# 04_CONNECTOR_OUT.net
KiCad netlist of a schematic drawn in Altium Designer
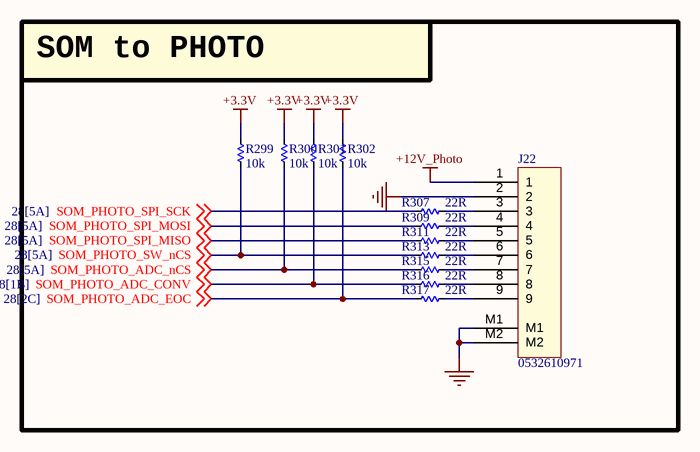
[diagram p0: 04_CONNECTOR_OUT.SchDoc]

(export (version "E")
  (design (tool "Eeschema 10.0.6"))
  (components
    (comp (ref "J22")
      (value "0532610971")
      (footprint "MOLEX_0532610971")
      (libsource (lib "LABLIB") (part "Header 9x1_2M"))
    )
    (comp (ref "R299")
      (value "10k")
      (footprint "RES_C_1005X40")
      (description "RES")
      (libsource (lib "LABLIB") (part "_RES_B_2"))
    )
    (comp (ref "R300")
      (value "10k")
      (footprint "RES_C_1005X40")
      (description "RES")
      (libsource (lib "LABLIB") (part "_RES_B_2"))
    )
    (comp (ref "R301")
      (value "10k")
      (footprint "RES_C_1005X40")
      (description "RES")
      (libsource (lib "LABLIB") (part "_RES_B_2"))
    )
    (comp (ref "R302")
      (value "10k")
      (footprint "RES_C_1005X40")
      (description "RES")
      (libsource (lib "LABLIB") (part "_RES_B_2"))
    )
    (comp (ref "R307")
      (value "22R")
      (footprint "RES_C_1005X40")
      (description "RES")
      (libsource (lib "LABLIB") (part "_RES_B_2"))
    )
    (comp (ref "R309")
      (value "22R")
      (footprint "RES_C_1005X40")
      (description "RES")
      (libsource (lib "LABLIB") (part "_RES_B_2"))
    )
    (comp (ref "R311")
      (value "22R")
      (footprint "RES_C_1005X40")
      (description "RES")
      (libsource (lib "LABLIB") (part "_RES_B_2"))
    )
    (comp (ref "R313")
      (value "22R")
      (footprint "RES_C_1005X40")
      (description "RES")
      (libsource (lib "LABLIB") (part "_RES_B_2"))
    )
    (comp (ref "R315")
      (value "22R")
      (footprint "RES_C_1005X40")
      (description "RES")
      (libsource (lib "LABLIB") (part "_RES_B_2"))
    )
    (comp (ref "R316")
      (value "22R")
      (footprint "RES_C_1005X40")
      (description "RES")
      (libsource (lib "LABLIB") (part "_RES_B_2"))
    )
    (comp (ref "R317")
      (value "22R")
      (footprint "RES_C_1005X40")
      (description "RES")
      (libsource (lib "LABLIB") (part "_RES_B_2"))
    )
  )
  (nets
    (net (code "1") (name "+3.3V") (class "Default")
      (node (ref "R299") (pin "1") (pinfunction "1_1") (pintype "passive"))
      (node (ref "R300") (pin "1") (pinfunction "1_1") (pintype "passive"))
      (node (ref "R301") (pin "1") (pinfunction "1_1") (pintype "passive"))
      (node (ref "R302") (pin "1") (pinfunction "1_1") (pintype "passive"))
    )
    (net (code "2") (name "+12V_Photo") (class "Default")
      (node (ref "J22") (pin "1") (pinfunction "1_1") (pintype "passive"))
    )
    (net (code "3") (name "GND") (class "Default")
      (node (ref "J22") (pin "2") (pinfunction "2_2") (pintype "passive"))
      (node (ref "J22") (pin "M1") (pinfunction "M1_M1") (pintype "passive"))
      (node (ref "J22") (pin "M2") (pinfunction "M2_M2") (pintype "passive"))
    )
    (net (code "4") (name "Net-(J22-Pad3)") (class "Default")
      (node (ref "J22") (pin "3") (pinfunction "3_3") (pintype "passive"))
      (node (ref "R307") (pin "2") (pinfunction "2_2") (pintype "passive"))
    )
    (net (code "5") (name "Net-(J22-Pad4)") (class "Default")
      (node (ref "J22") (pin "4") (pinfunction "4_4") (pintype "passive"))
      (node (ref "R309") (pin "2") (pinfunction "2_2") (pintype "passive"))
    )
    (net (code "6") (name "Net-(J22-Pad5)") (class "Default")
      (node (ref "J22") (pin "5") (pinfunction "5_5") (pintype "passive"))
      (node (ref "R311") (pin "2") (pinfunction "2_2") (pintype "passive"))
    )
    (net (code "7") (name "Net-(J22-Pad6)") (class "Default")
      (node (ref "J22") (pin "6") (pinfunction "6_6") (pintype "passive"))
      (node (ref "R313") (pin "2") (pinfunction "2_2") (pintype "passive"))
    )
    (net (code "8") (name "Net-(J22-Pad7)") (class "Default")
      (node (ref "J22") (pin "7") (pinfunction "7_7") (pintype "passive"))
      (node (ref "R315") (pin "2") (pinfunction "2_2") (pintype "passive"))
    )
    (net (code "9") (name "Net-(J22-Pad8)") (class "Default")
      (node (ref "J22") (pin "8") (pinfunction "8_8") (pintype "passive"))
      (node (ref "R316") (pin "2") (pinfunction "2_2") (pintype "passive"))
    )
    (net (code "10") (name "Net-(J22-Pad9)") (class "Default")
      (node (ref "J22") (pin "9") (pinfunction "9_9") (pintype "passive"))
      (node (ref "R317") (pin "2") (pinfunction "2_2") (pintype "passive"))
    )
    (net (code "11") (name "SOM_PHOTO_ADC_CONV") (class "Default")
      (node (ref "R301") (pin "2") (pinfunction "2_2") (pintype "passive"))
      (node (ref "R316") (pin "1") (pinfunction "1_1") (pintype "passive"))
    )
    (net (code "12") (name "SOM_PHOTO_ADC_EOC") (class "Default")
      (node (ref "R302") (pin "2") (pinfunction "2_2") (pintype "passive"))
      (node (ref "R317") (pin "1") (pinfunction "1_1") (pintype "passive"))
    )
    (net (code "13") (name "SOM_PHOTO_ADC_nCS") (class "Default")
      (node (ref "R300") (pin "2") (pinfunction "2_2") (pintype "passive"))
      (node (ref "R315") (pin "1") (pinfunction "1_1") (pintype "passive"))
    )
    (net (code "14") (name "SOM_PHOTO_SPI_MISO") (class "Default")
      (node (ref "R311") (pin "1") (pinfunction "1_1") (pintype "passive"))
    )
    (net (code "15") (name "SOM_PHOTO_SPI_MOSI") (class "Default")
      (node (ref "R309") (pin "1") (pinfunction "1_1") (pintype "passive"))
    )
    (net (code "16") (name "SOM_PHOTO_SPI_SCK") (class "Default")
      (node (ref "R307") (pin "1") (pinfunction "1_1") (pintype "passive"))
    )
    (net (code "17") (name "SOM_PHOTO_SW_nCS") (class "Default")
      (node (ref "R299") (pin "2") (pinfunction "2_2") (pintype "passive"))
      (node (ref "R313") (pin "1") (pinfunction "1_1") (pintype "passive"))
    )
  )
)
